# Sheet7.net
KiCad netlist of a schematic drawn in Altium Designer
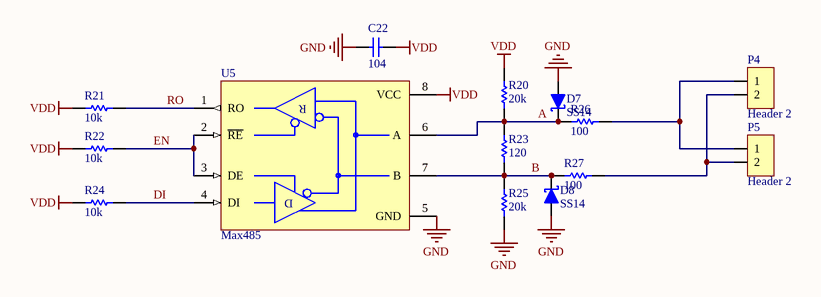
[diagram p0: Sheet7.SchDoc]

(export (version "E")
  (design (tool "Eeschema 10.0.6"))
  (components
    (comp (ref "C22")
      (value "104")
      (footprint "C 0805 (2012)")
      (description "Capacitor non-pol")
      (libsource (lib "BKIT4U_LIB") (part "Capacitor NP"))
    )
    (comp (ref "D7")
      (value "SS14")
      (footprint "DO-214AC (SMA)")
      (description "Schottky Diode")
      (fields (field (name "PUBLISHER") "Altium Limited"))
      (libsource (lib "BKIT4U_LIB") (part "Diode Schottky"))
    )
    (comp (ref "D8")
      (value "SS14")
      (footprint "DO-214AC (SMA)")
      (description "Schottky Diode")
      (fields (field (name "PUBLISHER") "Altium Limited"))
      (libsource (lib "BKIT4U_LIB") (part "Diode Schottky"))
    )
    (comp (ref "P4")
      (value "Header 2")
      (footprint "HDR Domino 2")
      (description "Header, 2-Pin")
      (fields (field (name "PUBLISHER") "Altium Limited"))
      (libsource (lib "BKIT4U_LIB") (part "Header 2"))
    )
    (comp (ref "P5")
      (value "Header 2")
      (footprint "HDR Domino 2")
      (description "Header, 2-Pin")
      (fields (field (name "PUBLISHER") "Altium Limited"))
      (libsource (lib "BKIT4U_LIB") (part "Header 2"))
    )
    (comp (ref "R20")
      (value "20k")
      (footprint "R 0805 (2012)")
      (description "Resistor")
      (fields (field (name "PUBLISHER") "Altium Limited"))
      (libsource (lib "BKIT4U_LIB") (part "Resistor"))
    )
    (comp (ref "R21")
      (value "10k")
      (footprint "R 0805 (2012)")
      (description "Resistor")
      (fields (field (name "PUBLISHER") "Altium Limited"))
      (libsource (lib "BKIT4U_LIB") (part "Resistor"))
    )
    (comp (ref "R22")
      (value "10k")
      (footprint "R 0805 (2012)")
      (description "Resistor")
      (fields (field (name "PUBLISHER") "Altium Limited"))
      (libsource (lib "BKIT4U_LIB") (part "Resistor"))
    )
    (comp (ref "R23")
      (value "120")
      (footprint "R 0805 (2012)")
      (description "Resistor")
      (fields (field (name "PUBLISHER") "Altium Limited"))
      (libsource (lib "BKIT4U_LIB") (part "Resistor"))
    )
    (comp (ref "R24")
      (value "10k")
      (footprint "R 0805 (2012)")
      (description "Resistor")
      (fields (field (name "PUBLISHER") "Altium Limited"))
      (libsource (lib "BKIT4U_LIB") (part "Resistor"))
    )
    (comp (ref "R25")
      (value "20k")
      (footprint "R 0805 (2012)")
      (description "Resistor")
      (fields (field (name "PUBLISHER") "Altium Limited"))
      (libsource (lib "BKIT4U_LIB") (part "Resistor"))
    )
    (comp (ref "R26")
      (value "100")
      (footprint "R 0805 (2012)")
      (description "Resistor")
      (fields (field (name "PUBLISHER") "Altium Limited"))
      (libsource (lib "BKIT4U_LIB") (part "Resistor"))
    )
    (comp (ref "R27")
      (value "100")
      (footprint "R 0805 (2012)")
      (description "Resistor")
      (fields (field (name "PUBLISHER") "Altium Limited"))
      (libsource (lib "BKIT4U_LIB") (part "Resistor"))
    )
    (comp (ref "U5") (value "Max485") (footprint "SOIC-8") (libsource (lib "BKIT4U_LIB") (part "MAX485")))
  )
  (nets
    (net (code "1") (name "/A") (class "Default")
      (node (ref "D7") (pin "2") (pinfunction "K_2") (pintype "passive"))
      (node (ref "R20") (pin "1") (pinfunction "1_1") (pintype "passive"))
      (node (ref "R23") (pin "2") (pinfunction "2_2") (pintype "passive"))
      (node (ref "R26") (pin "2") (pinfunction "2_2") (pintype "passive"))
      (node (ref "U5") (pin "6") (pinfunction "A_6") (pintype "passive"))
    )
    (net (code "2") (name "/B") (class "Default")
      (node (ref "D8") (pin "2") (pinfunction "K_2") (pintype "passive"))
      (node (ref "R23") (pin "1") (pinfunction "1_1") (pintype "passive"))
      (node (ref "R25") (pin "2") (pinfunction "2_2") (pintype "passive"))
      (node (ref "R27") (pin "2") (pinfunction "2_2") (pintype "passive"))
      (node (ref "U5") (pin "7") (pinfunction "B_7") (pintype "passive"))
    )
    (net (code "3") (name "/DI") (class "Default")
      (node (ref "R24") (pin "1") (pinfunction "1_1") (pintype "passive"))
      (node (ref "U5") (pin "4") (pinfunction "DI_4") (pintype "input"))
    )
    (net (code "4") (name "/EN") (class "Default")
      (node (ref "R22") (pin "1") (pinfunction "1_1") (pintype "passive"))
      (node (ref "U5") (pin "2") (pinfunction "~{RE}_2") (pintype "input"))
      (node (ref "U5") (pin "3") (pinfunction "DE_3") (pintype "input"))
    )
    (net (code "5") (name "/RO") (class "Default")
      (node (ref "R21") (pin "1") (pinfunction "1_1") (pintype "passive"))
      (node (ref "U5") (pin "1") (pinfunction "RO_1") (pintype "output"))
    )
    (net (code "6") (name "GND") (class "Default")
      (node (ref "C22") (pin "2") (pinfunction "2_2") (pintype "passive"))
      (node (ref "D7") (pin "1") (pinfunction "A_1") (pintype "passive"))
      (node (ref "D8") (pin "1") (pinfunction "A_1") (pintype "passive"))
      (node (ref "R25") (pin "1") (pinfunction "1_1") (pintype "passive"))
      (node (ref "U5") (pin "5") (pinfunction "GND_5") (pintype "power_in"))
    )
    (net (code "7") (name "Net-(P4-Pad1)") (class "Default")
      (node (ref "P4") (pin "1") (pinfunction "1_1") (pintype "passive"))
      (node (ref "P5") (pin "1") (pinfunction "1_1") (pintype "passive"))
      (node (ref "R26") (pin "1") (pinfunction "1_1") (pintype "passive"))
    )
    (net (code "8") (name "Net-(P4-Pad2)") (class "Default")
      (node (ref "P4") (pin "2") (pinfunction "2_2") (pintype "passive"))
      (node (ref "P5") (pin "2") (pinfunction "2_2") (pintype "passive"))
      (node (ref "R27") (pin "1") (pinfunction "1_1") (pintype "passive"))
    )
    (net (code "9") (name "VDD") (class "Default")
      (node (ref "C22") (pin "1") (pinfunction "1_1") (pintype "passive"))
      (node (ref "R20") (pin "2") (pinfunction "2_2") (pintype "passive"))
      (node (ref "R21") (pin "2") (pinfunction "2_2") (pintype "passive"))
      (node (ref "R22") (pin "2") (pinfunction "2_2") (pintype "passive"))
      (node (ref "R24") (pin "2") (pinfunction "2_2") (pintype "passive"))
      (node (ref "U5") (pin "8") (pinfunction "VCC_8") (pintype "passive"))
    )
  )
)
